# m12_eth.net
KiCad netlist of a schematic drawn in Altium Designer
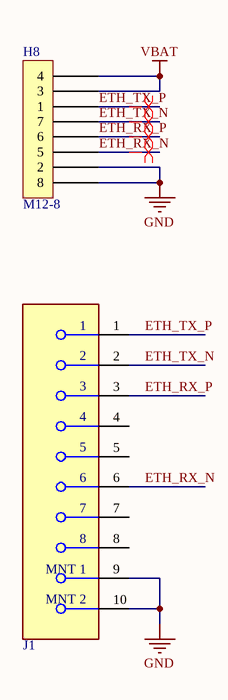
[diagram p0: m12_eth.SchDoc]

(export (version "E")
  (design (tool "Eeschema 10.0.6"))
  (components
    (comp (ref "H8")
      (value "M12-8")
      (footprint "861-008-113R004")
      (description "CONN RCPT MALE 8POS GOLD SOLDER")
      (fields
        (field (name "MANUFACTURER") "NorComp")
        (field (name "MANUFACTURER PART NUMBER") "861-008-113R004")
      )
      (libsource (lib "food_box") (part "TERM_8P"))
    )
    (comp (ref "J1")
      (value "RJLSE4238101T")
      (footprint "RJ45")
      (description "CONN MOD JACK 8P8C R/A SHIELDED")
      (fields (field (name "MANUFACTURER") "Amphenol Commercial"))
      (libsource (lib "food_box") (part "RJLSE4238101T"))
    )
  )
  (nets
    (net (code "1") (name "/ETH_RX_N") (class "Default")
      (node (ref "H8") (pin "5") (pinfunction "5_5") (pintype "passive"))
      (node (ref "J1") (pin "6") (pinfunction "6_6") (pintype "passive"))
    )
    (net (code "2") (name "/ETH_RX_P") (class "Default")
      (node (ref "H8") (pin "6") (pinfunction "6_6") (pintype "passive"))
      (node (ref "J1") (pin "3") (pinfunction "3_3") (pintype "passive"))
    )
    (net (code "3") (name "/ETH_TX_N") (class "Default")
      (node (ref "H8") (pin "7") (pinfunction "7_7") (pintype "passive"))
      (node (ref "J1") (pin "2") (pinfunction "2_2") (pintype "passive"))
    )
    (net (code "4") (name "/ETH_TX_P") (class "Default")
      (node (ref "H8") (pin "1") (pinfunction "1_1") (pintype "passive"))
      (node (ref "J1") (pin "1") (pinfunction "1_1") (pintype "passive"))
    )
    (net (code "5") (name "GND") (class "Default")
      (node (ref "H8") (pin "2") (pinfunction "2_2") (pintype "passive"))
      (node (ref "H8") (pin "8") (pinfunction "8_8") (pintype "passive"))
      (node (ref "J1") (pin "10") (pinfunction "MNT_2_10") (pintype "passive"))
      (node (ref "J1") (pin "9") (pinfunction "MNT_1_9") (pintype "passive"))
    )
    (net (code "6") (name "VBAT") (class "Default")
      (node (ref "H8") (pin "3") (pinfunction "3_3") (pintype "power_in"))
      (node (ref "H8") (pin "4") (pinfunction "4_4") (pintype "power_in"))
    )
    (net (code "7") (name "unconnected-(J1-Pad4)") (class "Default")
      (node (ref "J1") (pin "4") (pinfunction "4_4") (pintype "passive"))
    )
    (net (code "8") (name "unconnected-(J1-Pad5)") (class "Default")
      (node (ref "J1") (pin "5") (pinfunction "5_5") (pintype "passive"))
    )
    (net (code "9") (name "unconnected-(J1-Pad7)") (class "Default")
      (node (ref "J1") (pin "7") (pinfunction "7_7") (pintype "passive"))
    )
    (net (code "10") (name "unconnected-(J1-Pad8)") (class "Default")
      (node (ref "J1") (pin "8") (pinfunction "8_8") (pintype "passive"))
    )
  )
)
